# ServoSurucuSematik.net
KiCad netlist of a schematic drawn in Altium Designer
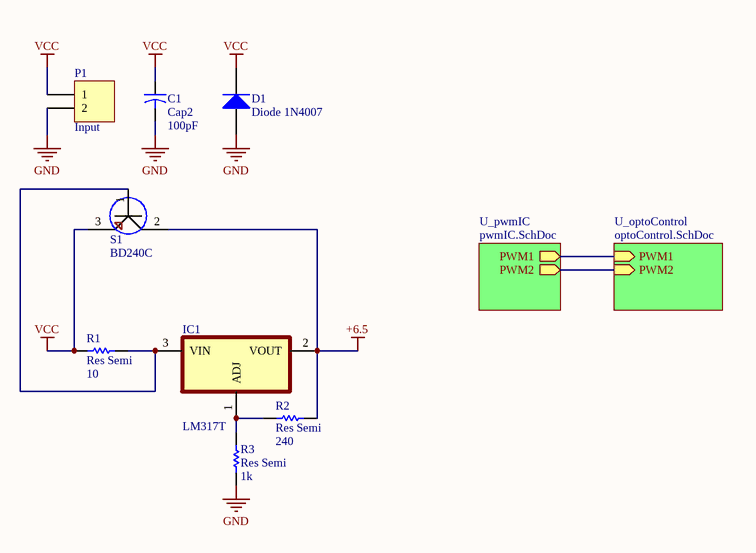
[diagram p0: ServoSurucuSematik.SchDoc]

(export (version "E")
  (design (tool "Eeschema 10.0.6"))
  (components
    (comp (ref "C1")
      (value "Cap2")
      (footprint "CAPR5-4X5")
      (description "Capacitor")
      (fields (field (name "ALTIUM_VALUE") "100pF") (field (name "PUBLISHER") "Altium Limited"))
      (libsource (lib "Miscellaneous Devices") (part "Cap2"))
    )
    (comp (ref "D1")
      (value "Diode 1N4007")
      (footprint "DO-41")
      (description "1 Amp General Purpose Rectifier")
      (fields (field (name "PUBLISHER") "Altium Limited"))
      (libsource (lib "Miscellaneous Devices") (part "Diode 1N4007"))
    )
    (comp (ref "IC1")
      (value "LM317T")
      (footprint "LM317")
      (description "1.5-A, 40-V, adjustable linear voltage regulator 3-TO-220")
      (fields (field (name "MF") "Texas Instruments"))
      (libsource (lib "RoketAnaSistemSematikKütüphane") (part "LM317T"))
    )
    (comp (ref "P1")
      (value "Input")
      (footprint "HDR1X2")
      (description "Header, 2-Pin")
      (fields (field (name "PUBLISHER") "Altium Limited"))
      (libsource (lib "Miscellaneous Connectors") (part "Header 2"))
    )
    (comp (ref "R1")
      (value "Res Semi")
      (footprint "AXIAL-0.5")
      (description "Semiconductor Resistor")
      (fields (field (name "ALTIUM_VALUE") "10") (field (name "PUBLISHER") "Altium Limited"))
      (libsource (lib "Miscellaneous Devices") (part "Res Semi"))
    )
    (comp (ref "R2")
      (value "Res Semi")
      (footprint "AXIAL-0.5")
      (description "Semiconductor Resistor")
      (fields (field (name "ALTIUM_VALUE") "240") (field (name "PUBLISHER") "Altium Limited"))
      (libsource (lib "Miscellaneous Devices") (part "Res Semi"))
    )
    (comp (ref "R3")
      (value "Res Semi")
      (footprint "AXIAL-0.5")
      (description "Semiconductor Resistor")
      (fields (field (name "ALTIUM_VALUE") "1k") (field (name "PUBLISHER") "Altium Limited"))
      (libsource (lib "Miscellaneous Devices") (part "Res Semi"))
    )
    (comp (ref "S1")
      (value "BD240C")
      (footprint "BD240C")
      (description "TO 220")
      (libsource (lib "RoketAnaSistemSematikKütüphane") (part "BD240C"))
    )
  )
  (nets
    (net (code "1") (name "+6.5") (class "Default")
      (node (ref "IC1") (pin "2") (pinfunction "VOUT_2") (pintype "passive"))
      (node (ref "R2") (pin "1") (pinfunction "1_1") (pintype "passive"))
      (node (ref "S1") (pin "2") (pintype "passive"))
    )
    (net (code "4") (name "GND") (class "Default")
      (node (ref "C1") (pin "2") (pinfunction "2_2") (pintype "passive"))
      (node (ref "D1") (pin "1") (pinfunction "A_1") (pintype "passive"))
      (node (ref "P1") (pin "2") (pinfunction "2_2") (pintype "passive"))
      (node (ref "R3") (pin "2") (pinfunction "2_2") (pintype "passive"))
    )
    (net (code "5") (name "Net-(IC1-ADJ)") (class "Default")
      (node (ref "IC1") (pin "1") (pinfunction "ADJ_1") (pintype "passive"))
      (node (ref "R2") (pin "2") (pinfunction "2_2") (pintype "passive"))
      (node (ref "R3") (pin "1") (pinfunction "1_1") (pintype "passive"))
    )
    (net (code "6") (name "Net-(IC1-VIN)") (class "Default")
      (node (ref "IC1") (pin "3") (pinfunction "VIN_3") (pintype "passive"))
      (node (ref "R1") (pin "1") (pinfunction "1_1") (pintype "passive"))
      (node (ref "S1") (pin "1") (pintype "passive"))
    )
    (net (code "7") (name "VCC") (class "Default")
      (node (ref "C1") (pin "1") (pinfunction "1_1") (pintype "passive"))
      (node (ref "D1") (pin "2") (pinfunction "K_2") (pintype "passive"))
      (node (ref "P1") (pin "1") (pinfunction "1_1") (pintype "passive"))
      (node (ref "R1") (pin "2") (pinfunction "2_2") (pintype "passive"))
      (node (ref "S1") (pin "3") (pintype "passive"))
    )
  )
)
